# StepperLogic.net
KiCad netlist of a schematic drawn in Altium Designer
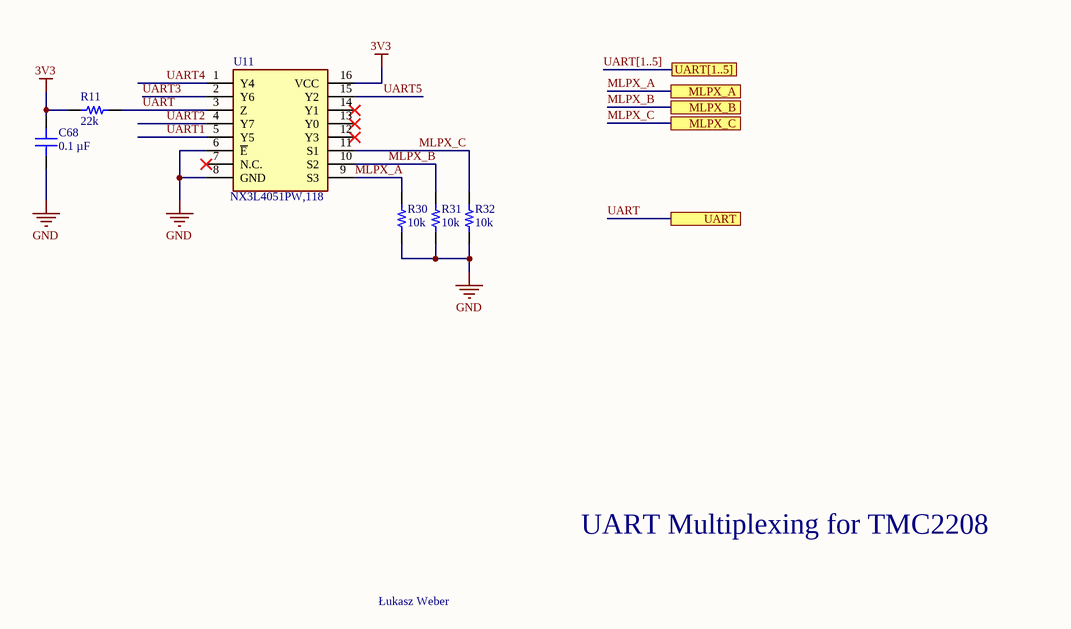
[diagram p0: StepperLogic.SchDoc]

(export (version "E")
  (design (tool "Eeschema 10.0.6"))
  (components
    (comp (ref "C68")
      (value "0.1 µF")
      (footprint "CAP 0603_1608")
      (description "CAP CER 0.1UF 100V X7R 0603")
      (fields
        (field (name "PART NUMBER") "0603B104K101CT")
        (field (name "MANUFACTURER") "Walsin Technology Corporation")
      )
      (libsource (lib "Celestial Altium Library - altium_library") (part "Capacitor"))
    )
    (comp (ref "R11")
      (value "22k")
      (footprint "RES 0603_1608")
      (description "RES 20K OHM 1% 1/4W 0603")
      (fields
        (field (name "PART NUMBER") "ERJ-UP3F2002V")
        (field (name "MANUFACTURER") "Panasonic Electronic Components")
      )
      (libsource (lib "Celestial Altium Library - altium_library") (part "Resistor"))
    )
    (comp (ref "R30")
      (value "10k")
      (footprint "RES 0603_1608")
      (description "RES 10K OHM 1% 1/5W 0603")
      (fields (field (name "PART NUMBER") "RC0603FR-7W10KL") (field (name "MANUFACTURER") "Yageo"))
      (libsource (lib "Celestial Altium Library - altium_library") (part "Resistor"))
    )
    (comp (ref "R31")
      (value "10k")
      (footprint "RES 0603_1608")
      (description "RES 10K OHM 1% 1/5W 0603")
      (fields (field (name "PART NUMBER") "RC0603FR-7W10KL") (field (name "MANUFACTURER") "Yageo"))
      (libsource (lib "Celestial Altium Library - altium_library") (part "Resistor"))
    )
    (comp (ref "R32")
      (value "10k")
      (footprint "RES 0603_1608")
      (description "RES 10K OHM 1% 1/5W 0603")
      (fields (field (name "PART NUMBER") "RC0603FR-7W10KL") (field (name "MANUFACTURER") "Yageo"))
      (libsource (lib "Celestial Altium Library - altium_library") (part "Resistor"))
    )
    (comp (ref "U11")
      (value "NX3L4051PW,118")
      (footprint "Power Driver:SOP65P640X110-16N")
      (description "Integrated Circuit")
      (fields (field (name "MOUSER PART NUMBER") "771-NX3L4051PW118"))
      (libsource (lib "*") (part "NX3L4051PW,118"))
    )
  )
  (nets
    (net (code "1") (name "/MLPX_A") (class "Default")
      (node (ref "R30") (pin "1") (pinfunction "1_1") (pintype "passive"))
      (node (ref "U11") (pin "9") (pinfunction "S3_9") (pintype "passive"))
    )
    (net (code "2") (name "/MLPX_B") (class "Default")
      (node (ref "R31") (pin "1") (pinfunction "1_1") (pintype "passive"))
      (node (ref "U11") (pin "10") (pinfunction "S2_10") (pintype "passive"))
    )
    (net (code "3") (name "/MLPX_C") (class "Default")
      (node (ref "R32") (pin "1") (pinfunction "1_1") (pintype "passive"))
      (node (ref "U11") (pin "11") (pinfunction "S1_11") (pintype "passive"))
    )
    (net (code "4") (name "/UART") (class "Default")
      (node (ref "R11") (pin "1") (pinfunction "1_1") (pintype "passive"))
      (node (ref "U11") (pin "3") (pinfunction "Z_3") (pintype "passive"))
    )
    (net (code "5") (name "/UART1") (class "Default")
      (node (ref "U11") (pin "5") (pinfunction "Y5_5") (pintype "passive"))
    )
    (net (code "6") (name "/UART2") (class "Default")
      (node (ref "U11") (pin "4") (pinfunction "Y7_4") (pintype "passive"))
    )
    (net (code "7") (name "/UART3") (class "Default")
      (node (ref "U11") (pin "2") (pinfunction "Y6_2") (pintype "passive"))
    )
    (net (code "8") (name "/UART4") (class "Default")
      (node (ref "U11") (pin "1") (pinfunction "Y4_1") (pintype "passive"))
    )
    (net (code "9") (name "/UART5") (class "Default")
      (node (ref "U11") (pin "15") (pinfunction "Y2_15") (pintype "passive"))
    )
    (net (code "11") (name "3V3") (class "Default")
      (node (ref "C68") (pin "2") (pinfunction "2_2") (pintype "passive"))
      (node (ref "R11") (pin "2") (pinfunction "2_2") (pintype "passive"))
      (node (ref "U11") (pin "16") (pinfunction "VCC_16") (pintype "passive"))
    )
    (net (code "12") (name "GND") (class "Default")
      (node (ref "C68") (pin "1") (pinfunction "1_1") (pintype "passive"))
      (node (ref "R30") (pin "2") (pinfunction "2_2") (pintype "passive"))
      (node (ref "R31") (pin "2") (pinfunction "2_2") (pintype "passive"))
      (node (ref "R32") (pin "2") (pinfunction "2_2") (pintype "passive"))
      (node (ref "U11") (pin "6") (pinfunction "~{E}_6") (pintype "passive"))
      (node (ref "U11") (pin "8") (pinfunction "GND_8") (pintype "passive"))
    )
    (net (code "13") (name "unconnected-(U11-N.C.-Pad7)") (class "Default")
      (node (ref "U11") (pin "7") (pinfunction "N.C._7") (pintype "passive+no_connect"))
    )
    (net (code "14") (name "unconnected-(U11-Y0-Pad13)") (class "Default")
      (node (ref "U11") (pin "13") (pinfunction "Y0_13") (pintype "passive+no_connect"))
    )
    (net (code "15") (name "unconnected-(U11-Y1-Pad14)") (class "Default")
      (node (ref "U11") (pin "14") (pinfunction "Y1_14") (pintype "passive+no_connect"))
    )
    (net (code "16") (name "unconnected-(U11-Y3-Pad12)") (class "Default")
      (node (ref "U11") (pin "12") (pinfunction "Y3_12") (pintype "passive+no_connect"))
    )
  )
)
